# Ethernet.net
KiCad netlist of a schematic drawn in Altium Designer
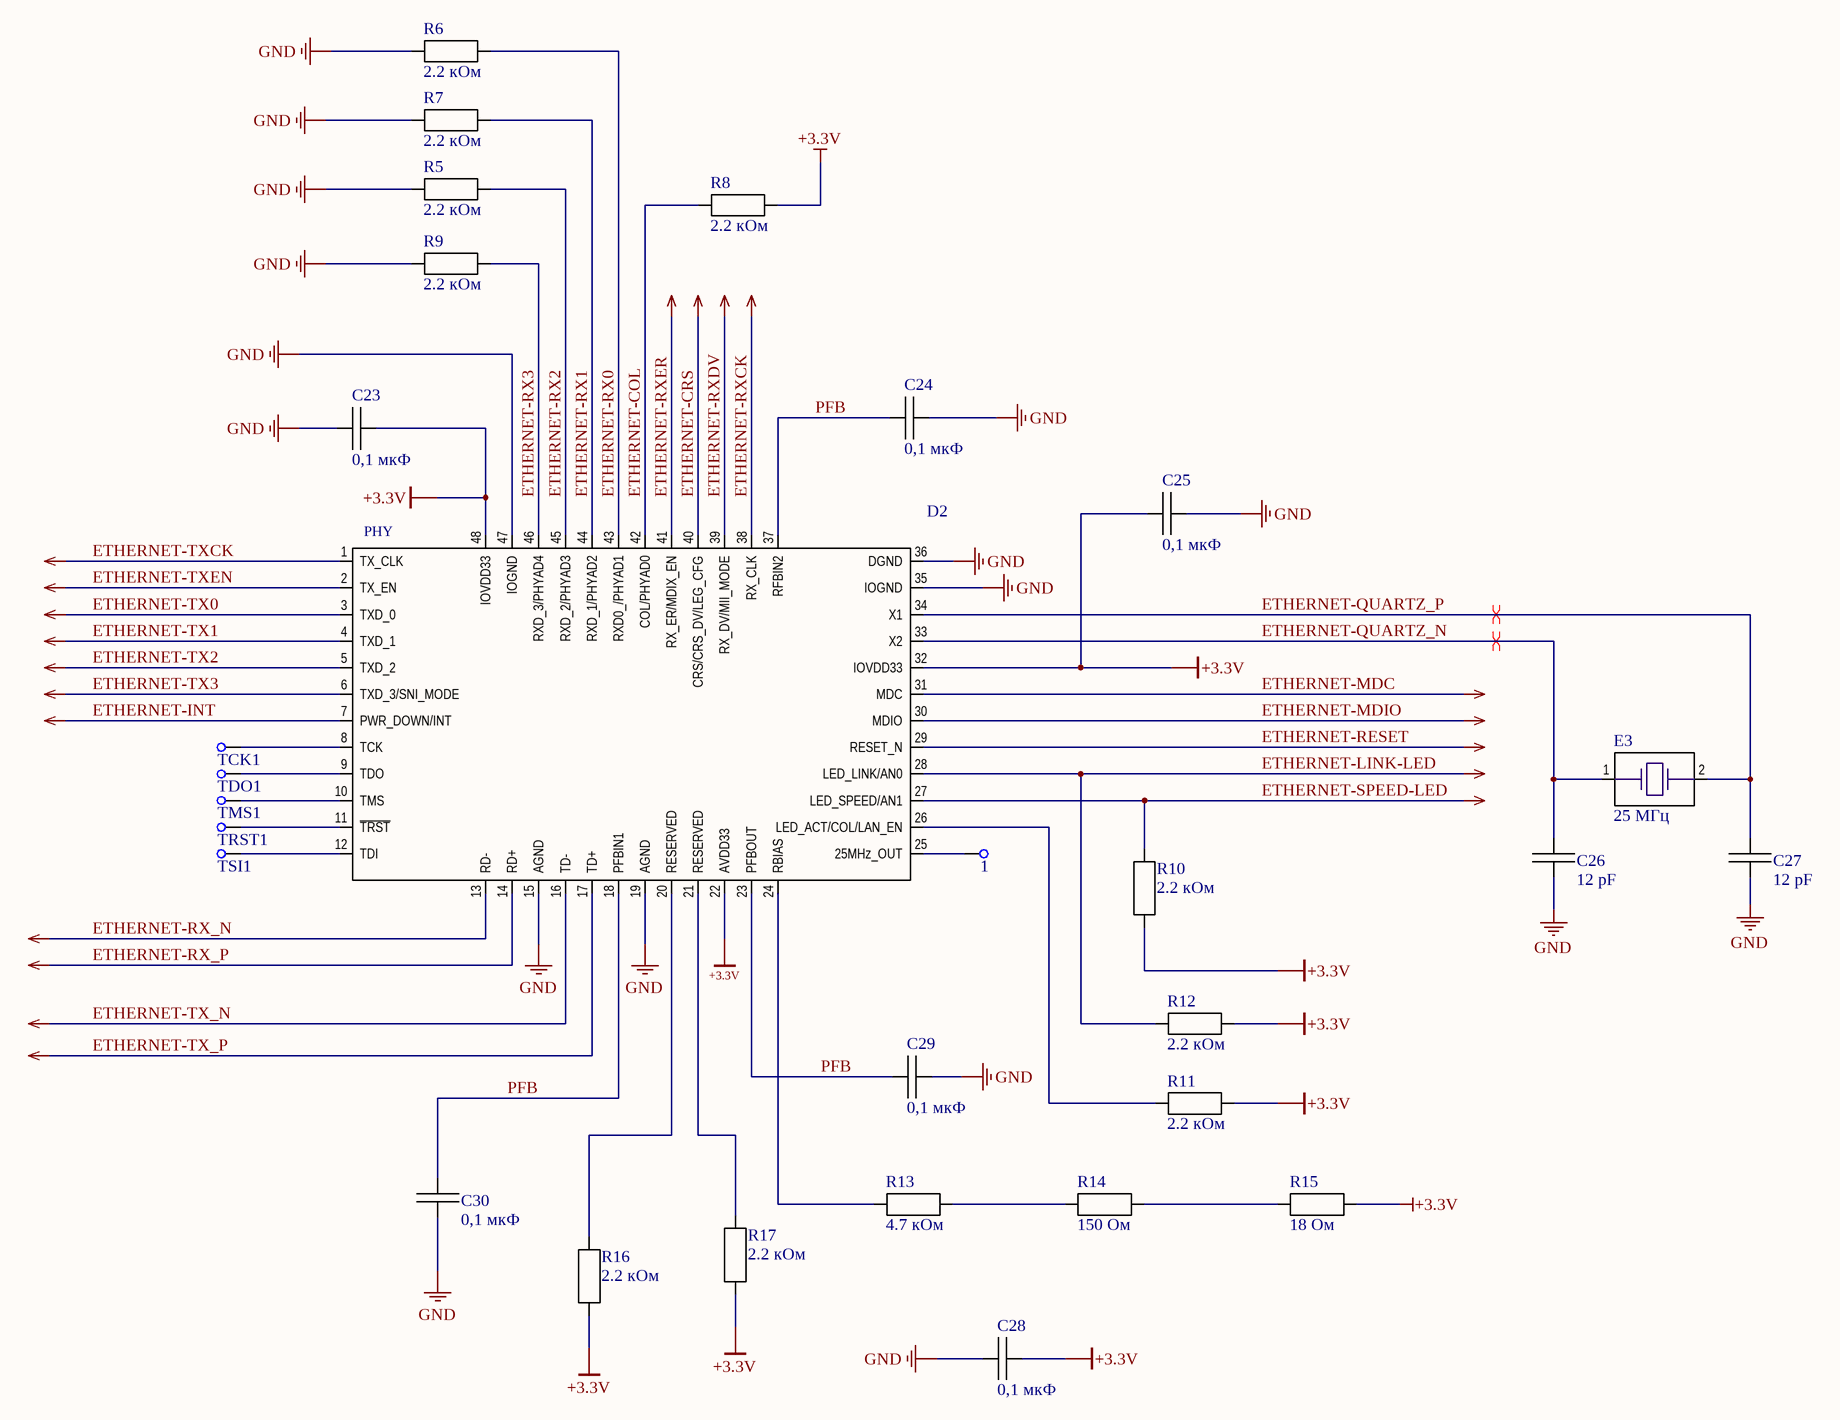
[diagram p0: Ethernet.SchDoc]

(export (version "E")
  (design (tool "Eeschema 10.0.6"))
  (components
    (comp (ref "1") (value "~") (footprint "PAD0,7X1.5") (libsource (lib "РАЗЪЕМЫ") (part "КП_0,7Х1,5")))
    (comp (ref "C23")
      (value "0,1 мкФ")
      (footprint "0603-AVX")
      (fields
        (field (name "MANUFACTURER") "AVX")
        (field (name "MANUFACTURERPARTNUMBER") "0603YC104KAT2A")
        (field (name "TOLERANCE") "±10%")
      )
      (libsource (lib "КОНДЕНСАТОРЫ") (part "0603-X7R-0,1мкФ-16В-10%"))
    )
    (comp (ref "C24")
      (value "0,1 мкФ")
      (footprint "0603-AVX")
      (fields
        (field (name "MANUFACTURER") "AVX")
        (field (name "MANUFACTURERPARTNUMBER") "0603YC104KAT2A")
        (field (name "TOLERANCE") "±10%")
      )
      (libsource (lib "КОНДЕНСАТОРЫ") (part "0603-X7R-0,1мкФ-16В-10%"))
    )
    (comp (ref "C25")
      (value "0,1 мкФ")
      (footprint "0603-AVX")
      (fields
        (field (name "MANUFACTURER") "AVX")
        (field (name "MANUFACTURERPARTNUMBER") "0603YC104KAT2A")
        (field (name "TOLERANCE") "±10%")
      )
      (libsource (lib "КОНДЕНСАТОРЫ") (part "0603-X7R-0,1мкФ-16В-10%"))
    )
    (comp (ref "C26")
      (value "12 pF")
      (footprint "0603-AVX")
      (fields
        (field (name "MANUFACTURER") "AVX")
        (field (name "MANUFACTURERPARTNUMBER") "06035C103KAT4A")
        (field (name "TOLERANCE") "±10%")
      )
      (libsource (lib "КОНДЕНСАТОРЫ") (part "0603-X7R-0,01мкФ-50В-10%"))
    )
    (comp (ref "C27")
      (value "12 pF")
      (footprint "0603-AVX")
      (fields
        (field (name "MANUFACTURER") "AVX")
        (field (name "MANUFACTURERPARTNUMBER") "06035C103KAT4A")
        (field (name "TOLERANCE") "±10%")
      )
      (libsource (lib "КОНДЕНСАТОРЫ") (part "0603-X7R-0,01мкФ-50В-10%"))
    )
    (comp (ref "C28")
      (value "0,1 мкФ")
      (footprint "0603-AVX")
      (fields
        (field (name "MANUFACTURER") "AVX")
        (field (name "MANUFACTURERPARTNUMBER") "0603YC104KAT2A")
        (field (name "TOLERANCE") "±10%")
      )
      (libsource (lib "КОНДЕНСАТОРЫ") (part "0603-X7R-0,1мкФ-16В-10%"))
    )
    (comp (ref "C29")
      (value "0,1 мкФ")
      (footprint "0603-AVX")
      (fields
        (field (name "MANUFACTURER") "AVX")
        (field (name "MANUFACTURERPARTNUMBER") "0603YC104KAT2A")
        (field (name "TOLERANCE") "±10%")
      )
      (libsource (lib "КОНДЕНСАТОРЫ") (part "0603-X7R-0,1мкФ-16В-10%"))
    )
    (comp (ref "C30")
      (value "0,1 мкФ")
      (footprint "0603-AVX")
      (fields
        (field (name "MANUFACTURER") "AVX")
        (field (name "MANUFACTURERPARTNUMBER") "0603YC104KAT2A")
        (field (name "TOLERANCE") "±10%")
      )
      (libsource (lib "КОНДЕНСАТОРЫ") (part "0603-X7R-0,1мкФ-16В-10%"))
    )
    (comp (ref "D2")
      (value "~")
      (footprint "S-PQFP-G48")
      (description "Ethernet physical layer transceiver")
      (fields
        (field (name "MANUFACTURER") "Texas Instruments")
        (field (name "MANUFACTURERPARTNUMBER") "DP83848")
      )
      (libsource (lib "МИКРОСХЕМЫ") (part "DP83848"))
    )
    (comp (ref "E3")
      (value "25 МГц")
      (footprint "HC49")
      (fields (field (name "MANUFACTURERPARTNUMBER") "Crystal oscillator 25Mhz"))
      (libsource (lib "МИКРОСХЕМЫ") (part "Crystal oscillator 25Mhz"))
    )
    (comp (ref "R5")
      (value "2.2 кОм")
      (footprint "Р1-8МП-0,125")
      (fields
        (field (name "TOLERANCE") "±1%-0,5-Л")
        (field (name "PARTNUMBER") "ОЖ0.467.164ТУ")
        (field (name "MANUFACTURERPARTNUMBER") "Р1-8МП-0,125-1 кОм±1%-0,5-Л")
      )
      (libsource (lib "РЕЗИСТОРЫ") (part "Р1-8МП-0,125-1 кОм±1%"))
    )
    (comp (ref "R6")
      (value "2.2 кОм")
      (footprint "Р1-8МП-0,125")
      (fields
        (field (name "TOLERANCE") "±1%-0,5-Л")
        (field (name "PARTNUMBER") "ОЖ0.467.164ТУ")
        (field (name "MANUFACTURERPARTNUMBER") "Р1-8МП-0,125-1 кОм±1%-0,5-Л")
      )
      (libsource (lib "РЕЗИСТОРЫ") (part "Р1-8МП-0,125-1 кОм±1%"))
    )
    (comp (ref "R7")
      (value "2.2 кОм")
      (footprint "Р1-8МП-0,125")
      (fields
        (field (name "TOLERANCE") "±1%-0,5-Л")
        (field (name "PARTNUMBER") "ОЖ0.467.164ТУ")
        (field (name "MANUFACTURERPARTNUMBER") "Р1-8МП-0,125-1 кОм±1%-0,5-Л")
      )
      (libsource (lib "РЕЗИСТОРЫ") (part "Р1-8МП-0,125-1 кОм±1%"))
    )
    (comp (ref "R8")
      (value "2.2 кОм")
      (footprint "Р1-8МП-0,125")
      (fields
        (field (name "TOLERANCE") "±1%-0,5-Л")
        (field (name "PARTNUMBER") "ОЖ0.467.164ТУ")
        (field (name "MANUFACTURERPARTNUMBER") "Р1-8МП-0,125-1 кОм±1%-0,5-Л")
      )
      (libsource (lib "РЕЗИСТОРЫ") (part "Р1-8МП-0,125-1 кОм±1%"))
    )
    (comp (ref "R9")
      (value "2.2 кОм")
      (footprint "Р1-8МП-0,125")
      (fields
        (field (name "TOLERANCE") "±1%-0,5-Л")
        (field (name "PARTNUMBER") "ОЖ0.467.164ТУ")
        (field (name "MANUFACTURERPARTNUMBER") "Р1-8МП-0,125-1 кОм±1%-0,5-Л")
      )
      (libsource (lib "РЕЗИСТОРЫ") (part "Р1-8МП-0,125-1 кОм±1%"))
    )
    (comp (ref "R10")
      (value "2.2 кОм")
      (footprint "Р1-8МП-0,125")
      (fields
        (field (name "TOLERANCE") "±1%-0,5-Л")
        (field (name "PARTNUMBER") "ОЖ0.467.164ТУ")
        (field (name "MANUFACTURERPARTNUMBER") "Р1-8МП-0,125-1 кОм±1%-0,5-Л")
      )
      (libsource (lib "РЕЗИСТОРЫ") (part "Р1-8МП-0,125-1 кОм±1%"))
    )
    (comp (ref "R11")
      (value "2.2 кОм")
      (footprint "Р1-8МП-0,125")
      (fields
        (field (name "TOLERANCE") "±1%-0,5-Л")
        (field (name "PARTNUMBER") "ОЖ0.467.164ТУ")
        (field (name "MANUFACTURERPARTNUMBER") "Р1-8МП-0,125-1 кОм±1%-0,5-Л")
      )
      (libsource (lib "РЕЗИСТОРЫ") (part "Р1-8МП-0,125-1 кОм±1%"))
    )
    (comp (ref "R12")
      (value "2.2 кОм")
      (footprint "Р1-8МП-0,125")
      (fields
        (field (name "TOLERANCE") "±1%-0,5-Л")
        (field (name "PARTNUMBER") "ОЖ0.467.164ТУ")
        (field (name "MANUFACTURERPARTNUMBER") "Р1-8МП-0,125-1 кОм±1%-0,5-Л")
      )
      (libsource (lib "РЕЗИСТОРЫ") (part "Р1-8МП-0,125-1 кОм±1%"))
    )
    (comp (ref "R13")
      (value "4.7 кОм")
      (footprint "Р1-8МП-0,125")
      (fields
        (field (name "TOLERANCE") "±1%-0,5-Л")
        (field (name "PARTNUMBER") "ОЖ0.467.164ТУ")
        (field (name "MANUFACTURERPARTNUMBER") "Р1-8МП-0,125-1 кОм±1%-0,5-Л")
      )
      (libsource (lib "РЕЗИСТОРЫ") (part "Р1-8МП-0,125-1 кОм±1%"))
    )
    (comp (ref "R14")
      (value "150 Ом")
      (footprint "Р1-8МП-0,125")
      (fields
        (field (name "TOLERANCE") "±1%-0,5-Л")
        (field (name "PARTNUMBER") "ОЖ0.467.164ТУ")
        (field (name "MANUFACTURERPARTNUMBER") "Р1-8МП-0,125-1 кОм±1%-0,5-Л")
      )
      (libsource (lib "РЕЗИСТОРЫ") (part "Р1-8МП-0,125-1 кОм±1%"))
    )
    (comp (ref "R15")
      (value "18 Ом")
      (footprint "Р1-8МП-0,125")
      (fields
        (field (name "TOLERANCE") "±1%-0,5-Л")
        (field (name "PARTNUMBER") "ОЖ0.467.164ТУ")
        (field (name "MANUFACTURERPARTNUMBER") "Р1-8МП-0,125-1 кОм±1%-0,5-Л")
      )
      (libsource (lib "РЕЗИСТОРЫ") (part "Р1-8МП-0,125-1 кОм±1%"))
    )
    (comp (ref "R16")
      (value "2.2 кОм")
      (footprint "Р1-8МП-0,125")
      (fields
        (field (name "TOLERANCE") "±1%-0,5-Л")
        (field (name "PARTNUMBER") "ОЖ0.467.164ТУ")
        (field (name "MANUFACTURERPARTNUMBER") "Р1-8МП-0,125-1 кОм±1%-0,5-Л")
      )
      (libsource (lib "РЕЗИСТОРЫ") (part "Р1-8МП-0,125-1 кОм±1%"))
    )
    (comp (ref "R17")
      (value "2.2 кОм")
      (footprint "Р1-8МП-0,125")
      (fields
        (field (name "TOLERANCE") "±1%-0,5-Л")
        (field (name "PARTNUMBER") "ОЖ0.467.164ТУ")
        (field (name "MANUFACTURERPARTNUMBER") "Р1-8МП-0,125-1 кОм±1%-0,5-Л")
      )
      (libsource (lib "РЕЗИСТОРЫ") (part "Р1-8МП-0,125-1 кОм±1%"))
    )
    (comp (ref "TCK1") (value "~") (footprint "PAD0,7X1.5") (libsource (lib "РАЗЪЕМЫ") (part "КП_0,7Х1,5")))
    (comp (ref "TDO1") (value "~") (footprint "PAD0,7X1.5") (libsource (lib "РАЗЪЕМЫ") (part "КП_0,7Х1,5")))
    (comp (ref "TMS1") (value "~") (footprint "PAD0,7X1.5") (libsource (lib "РАЗЪЕМЫ") (part "КП_0,7Х1,5")))
    (comp (ref "TRST1") (value "~") (footprint "PAD0,7X1.5") (libsource (lib "РАЗЪЕМЫ") (part "КП_0,7Х1,5")))
    (comp (ref "TSI1") (value "~") (footprint "PAD0,7X1.5") (libsource (lib "РАЗЪЕМЫ") (part "КП_0,7Х1,5")))
  )
  (nets
    (net (code "1") (name "+3.3V") (class "Default")
      (node (ref "C23") (pin "2") (pinfunction "2_2") (pintype "passive"))
      (node (ref "C25") (pin "1") (pinfunction "1_1") (pintype "passive"))
      (node (ref "C28") (pin "2") (pinfunction "2_2") (pintype "passive"))
      (node (ref "D2") (pin "22") (pinfunction "AVDD33_22") (pintype "passive"))
      (node (ref "D2") (pin "32") (pinfunction "IOVDD33_32") (pintype "passive"))
      (node (ref "D2") (pin "48") (pinfunction "IOVDD33_48") (pintype "passive"))
      (node (ref "R10") (pin "2") (pinfunction "2_2") (pintype "passive"))
      (node (ref "R11") (pin "1") (pinfunction "1_1") (pintype "passive"))
      (node (ref "R12") (pin "1") (pinfunction "1_1") (pintype "passive"))
      (node (ref "R15") (pin "1") (pinfunction "1_1") (pintype "passive"))
      (node (ref "R16") (pin "2") (pinfunction "2_2") (pintype "passive"))
      (node (ref "R17") (pin "2") (pinfunction "2_2") (pintype "passive"))
      (node (ref "R8") (pin "1") (pinfunction "1_1") (pintype "passive"))
    )
    (net (code "2") (name "/ETHERNET-COL") (class "Default")
      (node (ref "D2") (pin "42") (pinfunction "COL/PHYAD0_42") (pintype "passive"))
      (node (ref "R8") (pin "2") (pinfunction "2_2") (pintype "passive"))
    )
    (net (code "3") (name "/ETHERNET-QUARTZ_N") (class "Default")
      (node (ref "C26") (pin "2") (pinfunction "2_2") (pintype "passive"))
      (node (ref "D2") (pin "33") (pinfunction "X2_33") (pintype "passive"))
      (node (ref "E3") (pin "1") (pintype "passive"))
    )
    (net (code "4") (name "/ETHERNET-QUARTZ_P") (class "Default")
      (node (ref "C27") (pin "2") (pinfunction "2_2") (pintype "passive"))
      (node (ref "D2") (pin "34") (pinfunction "X1_34") (pintype "passive"))
      (node (ref "E3") (pin "2") (pintype "passive"))
    )
    (net (code "5") (name "/ETHERNET-RX0") (class "Default")
      (node (ref "D2") (pin "43") (pinfunction "RXD0_/PHYAD1_43") (pintype "passive"))
      (node (ref "R6") (pin "2") (pinfunction "2_2") (pintype "passive"))
    )
    (net (code "6") (name "/ETHERNET-RX1") (class "Default")
      (node (ref "D2") (pin "44") (pinfunction "RXD_1/PHYAD2_44") (pintype "passive"))
      (node (ref "R7") (pin "2") (pinfunction "2_2") (pintype "passive"))
    )
    (net (code "7") (name "/ETHERNET-RX2") (class "Default")
      (node (ref "D2") (pin "45") (pinfunction "RXD_2/PHYAD3_45") (pintype "passive"))
      (node (ref "R5") (pin "2") (pinfunction "2_2") (pintype "passive"))
    )
    (net (code "8") (name "/ETHERNET-RX3") (class "Default")
      (node (ref "D2") (pin "46") (pinfunction "RXD_3/PHYAD4_46") (pintype "passive"))
      (node (ref "R9") (pin "2") (pinfunction "2_2") (pintype "passive"))
    )
    (net (code "9") (name "/PFB") (class "Default")
      (node (ref "C24") (pin "1") (pinfunction "1_1") (pintype "passive"))
      (node (ref "C29") (pin "2") (pinfunction "2_2") (pintype "passive"))
      (node (ref "C30") (pin "2") (pinfunction "2_2") (pintype "passive"))
      (node (ref "D2") (pin "18") (pinfunction "PFBIN1_18") (pintype "passive"))
      (node (ref "D2") (pin "23") (pinfunction "PFBOUT_23") (pintype "passive"))
      (node (ref "D2") (pin "37") (pinfunction "RFBIN2_37") (pintype "passive"))
    )
    (net (code "10") (name "<NO NET>") (class "Default")
      (node (ref "D2") (pin "1") (pinfunction "TX_CLK_1") (pintype "passive"))
      (node (ref "D2") (pin "13") (pinfunction "RD-_13") (pintype "passive"))
      (node (ref "D2") (pin "14") (pinfunction "RD+_14") (pintype "passive"))
      (node (ref "D2") (pin "16") (pinfunction "TD-_16") (pintype "passive"))
      (node (ref "D2") (pin "17") (pinfunction "TD+_17") (pintype "passive"))
      (node (ref "D2") (pin "2") (pinfunction "TX_EN_2") (pintype "passive"))
      (node (ref "D2") (pin "27") (pinfunction "LED_SPEED/AN1_27") (pintype "passive"))
      (node (ref "D2") (pin "28") (pinfunction "LED_LINK/AN0_28") (pintype "passive"))
      (node (ref "D2") (pin "29") (pinfunction "RESET_N_29") (pintype "passive"))
      (node (ref "D2") (pin "3") (pinfunction "TXD_0_3") (pintype "passive"))
      (node (ref "D2") (pin "30") (pinfunction "MDIO_30") (pintype "passive"))
      (node (ref "D2") (pin "31") (pinfunction "MDC_31") (pintype "passive"))
      (node (ref "D2") (pin "38") (pinfunction "RX_CLK_38") (pintype "passive"))
      (node (ref "D2") (pin "39") (pinfunction "RX_DV/MII_MODE_39") (pintype "passive"))
      (node (ref "D2") (pin "4") (pinfunction "TXD_1_4") (pintype "passive"))
      (node (ref "D2") (pin "40") (pinfunction "CRS/CRS_DV/LEG_CFG_40") (pintype "passive"))
      (node (ref "D2") (pin "41") (pinfunction "RX_ER/MDIX_EN_41") (pintype "passive"))
      (node (ref "D2") (pin "5") (pinfunction "TXD_2_5") (pintype "passive"))
      (node (ref "D2") (pin "6") (pinfunction "TXD_3/SNI_MODE_6") (pintype "passive"))
      (node (ref "D2") (pin "7") (pinfunction "PWR_DOWN/INT_7") (pintype "passive"))
      (node (ref "R10") (pin "1") (pinfunction "1_1") (pintype "passive"))
      (node (ref "R12") (pin "2") (pinfunction "2_2") (pintype "passive"))
    )
    (net (code "11") (name "GND") (class "Default")
      (node (ref "C23") (pin "1") (pinfunction "1_1") (pintype "passive"))
      (node (ref "C24") (pin "2") (pinfunction "2_2") (pintype "passive"))
      (node (ref "C25") (pin "2") (pinfunction "2_2") (pintype "passive"))
      (node (ref "C26") (pin "1") (pinfunction "1_1") (pintype "passive"))
      (node (ref "C27") (pin "1") (pinfunction "1_1") (pintype "passive"))
      (node (ref "C28") (pin "1") (pinfunction "1_1") (pintype "passive"))
      (node (ref "C29") (pin "1") (pinfunction "1_1") (pintype "passive"))
      (node (ref "C30") (pin "1") (pinfunction "1_1") (pintype "passive"))
      (node (ref "D2") (pin "15") (pinfunction "AGND_15") (pintype "passive"))
      (node (ref "D2") (pin "19") (pinfunction "AGND_19") (pintype "passive"))
      (node (ref "D2") (pin "35") (pinfunction "IOGND_35") (pintype "passive"))
      (node (ref "D2") (pin "36") (pinfunction "DGND_36") (pintype "passive"))
      (node (ref "D2") (pin "47") (pinfunction "IOGND_47") (pintype "passive"))
      (node (ref "R5") (pin "1") (pinfunction "1_1") (pintype "passive"))
      (node (ref "R6") (pin "1") (pinfunction "1_1") (pintype "passive"))
      (node (ref "R7") (pin "1") (pinfunction "1_1") (pintype "passive"))
      (node (ref "R9") (pin "1") (pinfunction "1_1") (pintype "passive"))
    )
    (net (code "12") (name "Net-(D2-25MHz_OUT)") (class "Default")
      (node (ref "1") (pin "1") (pinfunction "1_1") (pintype "passive"))
      (node (ref "D2") (pin "25") (pinfunction "25MHz_OUT_25") (pintype "passive"))
    )
    (net (code "13") (name "Net-(D2-LED_ACT{slash}COL{slash}LAN_EN)") (class "Default")
      (node (ref "D2") (pin "26") (pinfunction "LED_ACT/COL/LAN_EN_26") (pintype "passive"))
      (node (ref "R11") (pin "2") (pinfunction "2_2") (pintype "passive"))
    )
    (net (code "14") (name "Net-(D2-RBIAS)") (class "Default")
      (node (ref "D2") (pin "24") (pinfunction "RBIAS_24") (pintype "passive"))
      (node (ref "R13") (pin "2") (pinfunction "2_2") (pintype "passive"))
    )
    (net (code "15") (name "Net-(D2-RESERVED-Pad20)") (class "Default")
      (node (ref "D2") (pin "20") (pinfunction "RESERVED_20") (pintype "passive"))
      (node (ref "R16") (pin "1") (pinfunction "1_1") (pintype "passive"))
    )
    (net (code "16") (name "Net-(D2-RESERVED-Pad21)") (class "Default")
      (node (ref "D2") (pin "21") (pinfunction "RESERVED_21") (pintype "passive"))
      (node (ref "R17") (pin "1") (pinfunction "1_1") (pintype "passive"))
    )
    (net (code "17") (name "Net-(D2-TCK)") (class "Default")
      (node (ref "D2") (pin "8") (pinfunction "TCK_8") (pintype "passive"))
      (node (ref "TCK1") (pin "1") (pinfunction "1_1") (pintype "passive"))
    )
    (net (code "18") (name "Net-(D2-TDI)") (class "Default")
      (node (ref "D2") (pin "12") (pinfunction "TDI_12") (pintype "passive"))
      (node (ref "TSI1") (pin "1") (pinfunction "1_1") (pintype "passive"))
    )
    (net (code "19") (name "Net-(D2-TDO)") (class "Default")
      (node (ref "D2") (pin "9") (pinfunction "TDO_9") (pintype "passive"))
      (node (ref "TDO1") (pin "1") (pinfunction "1_1") (pintype "passive"))
    )
    (net (code "20") (name "Net-(D2-TMS)") (class "Default")
      (node (ref "D2") (pin "10") (pinfunction "TMS_10") (pintype "passive"))
      (node (ref "TMS1") (pin "1") (pinfunction "1_1") (pintype "passive"))
    )
    (net (code "21") (name "Net-(D2-~{TRST})") (class "Default")
      (node (ref "D2") (pin "11") (pinfunction "~{TRST}_11") (pintype "passive"))
      (node (ref "TRST1") (pin "1") (pinfunction "1_1") (pintype "passive"))
    )
    (net (code "22") (name "Net-(R13-Pad1)") (class "Default")
      (node (ref "R13") (pin "1") (pinfunction "1_1") (pintype "passive"))
      (node (ref "R14") (pin "2") (pinfunction "2_2") (pintype "passive"))
    )
    (net (code "23") (name "Net-(R14-Pad1)") (class "Default")
      (node (ref "R14") (pin "1") (pinfunction "1_1") (pintype "passive"))
      (node (ref "R15") (pin "2") (pinfunction "2_2") (pintype "passive"))
    )
  )
)
